# RainbowClock.net
KiCad netlist of a schematic drawn in Altium Designer
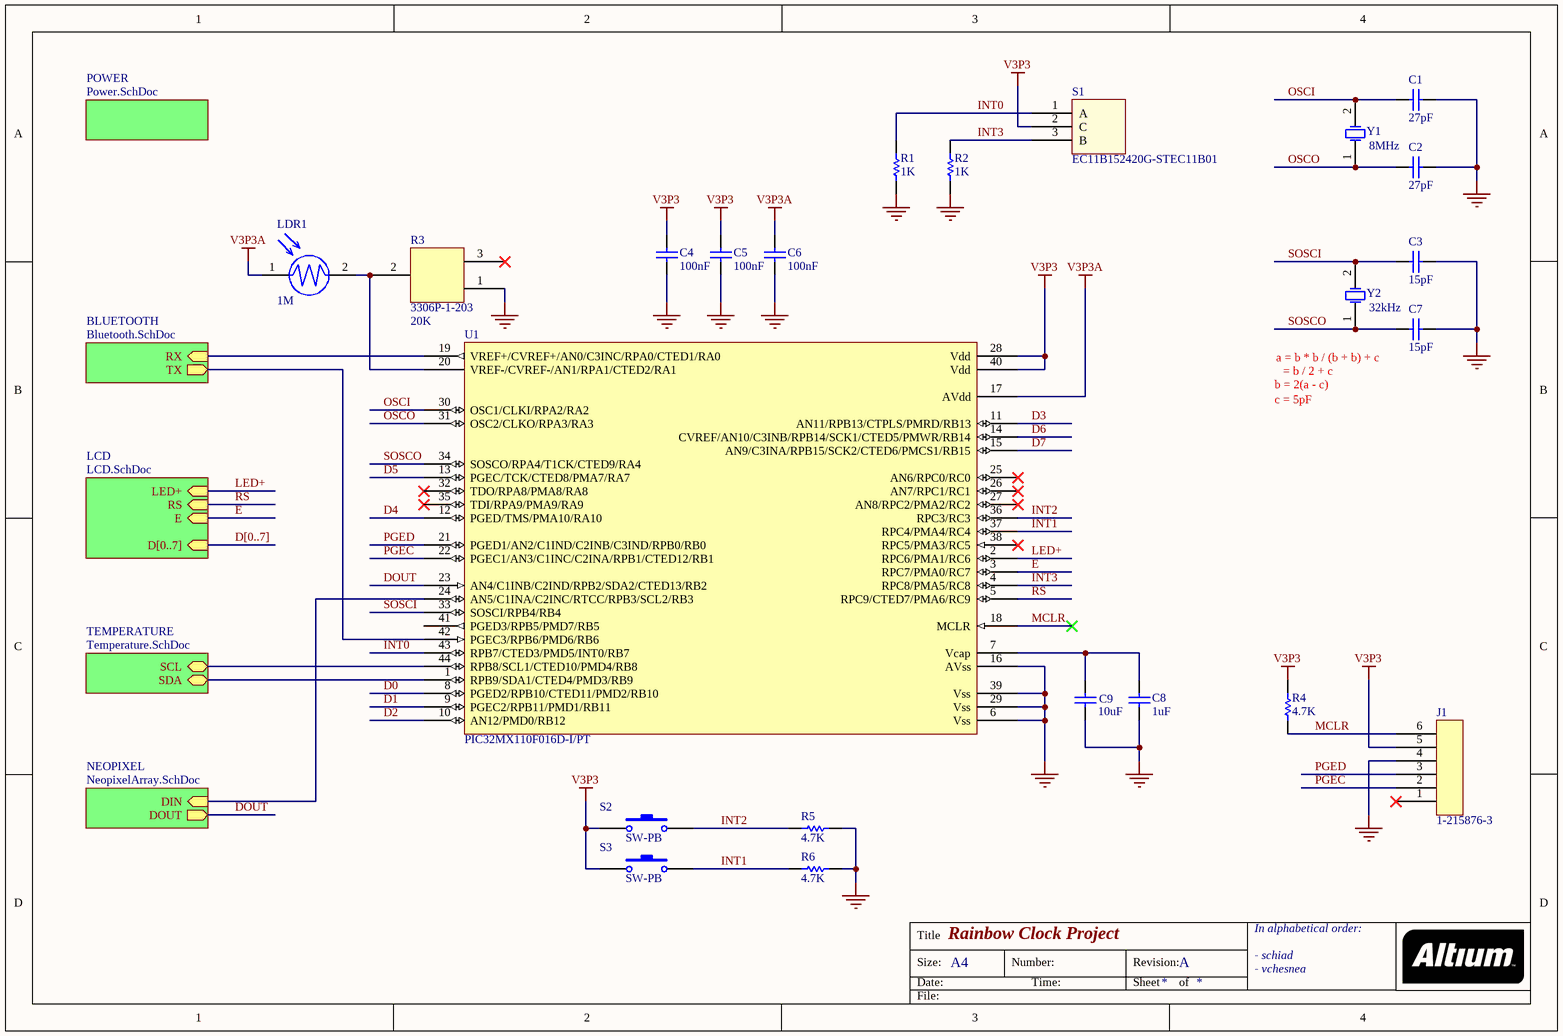
[diagram p0: RainbowClock.SchDoc]

(export (version "E")
  (design (tool "Eeschema 10.0.6"))
  (components
    (comp (ref "C1")
      (value "27pF")
      (footprint "CAP0603")
      (description "Capacitor")
      (libsource (lib "Miscellaneous Devices") (part "Cap"))
    )
    (comp (ref "C2")
      (value "27pF")
      (footprint "CAP0603")
      (description "Capacitor")
      (libsource (lib "Miscellaneous Devices") (part "Cap"))
    )
    (comp (ref "C3")
      (value "15pF")
      (footprint "CAP0603")
      (description "Capacitor")
      (libsource (lib "Miscellaneous Devices") (part "Cap"))
    )
    (comp (ref "C4")
      (value "100nF")
      (footprint "CAP0603")
      (description "Capacitor")
      (libsource (lib "Miscellaneous Devices") (part "Cap"))
    )
    (comp (ref "C5")
      (value "100nF")
      (footprint "CAP0603")
      (description "Capacitor")
      (libsource (lib "Miscellaneous Devices") (part "Cap"))
    )
    (comp (ref "C6")
      (value "100nF")
      (footprint "CAP0603")
      (description "Capacitor")
      (libsource (lib "Miscellaneous Devices") (part "Cap"))
    )
    (comp (ref "C7")
      (value "15pF")
      (footprint "CAP0603")
      (description "Capacitor")
      (libsource (lib "Miscellaneous Devices") (part "Cap"))
    )
    (comp (ref "C8")
      (value "1uF")
      (footprint "CAP0603")
      (description "Capacitor")
      (libsource (lib "Miscellaneous Devices") (part "Cap"))
    )
    (comp (ref "C9")
      (value "10uF")
      (footprint "CAP0603")
      (description "Capacitor")
      (libsource (lib "Miscellaneous Devices") (part "Cap"))
    )
    (comp (ref "J1")
      (value "1-215876-3")
      (footprint "1-215876-3")
      (description "Tyco 1-215876-3")
      (libsource (lib "Components") (part "1-215876-3"))
    )
    (comp (ref "LDR1")
      (value "1M")
      (footprint "VT935G")
      (description "Photoresistor")
      (fields (field (name "Comment") "LDR"))
      (libsource (lib "Components") (part "LDR"))
    )
    (comp (ref "R1")
      (value "1K")
      (footprint "RES0603")
      (description "Resistor")
      (libsource (lib "Miscellaneous Devices") (part "Res1"))
    )
    (comp (ref "R2")
      (value "1K")
      (footprint "RES0603")
      (description "Resistor")
      (libsource (lib "Miscellaneous Devices") (part "Res1"))
    )
    (comp (ref "R3")
      (value "3306P-1-203")
      (footprint "3306P-1-202")
      (description "Trimpot")
      (fields (field (name "ALTIUM_VALUE") "20K"))
      (libsource (lib "Components") (part "3306P-1-202"))
    )
    (comp (ref "R4")
      (value "4.7K")
      (footprint "RES0603")
      (description "Resistor")
      (libsource (lib "Miscellaneous Devices") (part "Res1"))
    )
    (comp (ref "R5")
      (value "4.7K")
      (footprint "RES0603")
      (description "Resistor")
      (libsource (lib "Miscellaneous Devices") (part "Res1"))
    )
    (comp (ref "R6")
      (value "4.7K")
      (footprint "RES0603")
      (description "Resistor")
      (libsource (lib "Miscellaneous Devices") (part "Res1"))
    )
    (comp (ref "S1")
      (value "EC11B152420G-STEC11B01")
      (footprint "EC11B152420G-STEC11B01")
      (description "Rotary encoder")
      (libsource (lib "Components") (part "EC11B152420G-STEC11B01"))
    )
    (comp (ref "S2")
      (value "SW-PB")
      (footprint "1-1825027-4")
      (description "Switch")
      (libsource (lib "Miscellaneous Devices") (part "SW-PB"))
    )
    (comp (ref "S3")
      (value "SW-PB")
      (footprint "1-1825027-4")
      (description "Switch")
      (libsource (lib "Miscellaneous Devices") (part "SW-PB"))
    )
    (comp (ref "U1")
      (value "PIC32MX110F016D-I/PT")
      (footprint "PIC32MX110F016H-I/PT")
      (description "Microcontroller")
      (libsource (lib "Components") (part "PIC32MX110F016D-I/PT"))
    )
    (comp (ref "Y1")
      (value "8MHz")
      (footprint "FOXSLF/080-20")
      (description "Crystal Oscillator")
      (fields (field (name "Comment") "8MHz XTAL"))
      (libsource (lib "Miscellaneous Devices") (part "XTAL"))
    )
    (comp (ref "Y2")
      (value "32kHz")
      (footprint "NCL38LF")
      (description "Crystal Oscillator")
      (fields (field (name "Comment") "32kHz XTAL"))
      (libsource (lib "Miscellaneous Devices") (part "XTAL"))
    )
  )
  (nets
    (net (code "1") (name "/D0") (class "Default")
      (node (ref "U1") (pin "8") (pinfunction "PGED2/RPB10/CTED11/PMD2/RB10_8") (pintype "bidirectional"))
    )
    (net (code "2") (name "/D1") (class "Default")
      (node (ref "U1") (pin "9") (pinfunction "PGEC2/RPB11/PMD1/RB11_9") (pintype "bidirectional"))
    )
    (net (code "3") (name "/D2") (class "Default")
      (node (ref "U1") (pin "10") (pinfunction "AN12/PMD0/RB12_10") (pintype "bidirectional"))
    )
    (net (code "4") (name "/D3") (class "Default")
      (node (ref "U1") (pin "11") (pinfunction "AN11/RPB13/CTPLS/PMRD/RB13_11") (pintype "bidirectional"))
    )
    (net (code "5") (name "/D4") (class "Default")
      (node (ref "U1") (pin "12") (pinfunction "PGED/TMS/PMA10/RA10_12") (pintype "bidirectional"))
    )
    (net (code "6") (name "/D5") (class "Default")
      (node (ref "U1") (pin "13") (pinfunction "PGEC/TCK/CTED8/PMA7/RA7_13") (pintype "bidirectional"))
    )
    (net (code "7") (name "/D6") (class "Default")
      (node (ref "U1") (pin "14") (pinfunction "CVREF/AN10/C3INB/RPB14/SCK1/CTED5/PMWR/RB14_14") (pintype "bidirectional"))
    )
    (net (code "8") (name "/D7") (class "Default")
      (node (ref "U1") (pin "15") (pinfunction "AN9/C3INA/RPB15/SCK2/CTED6/PMCS1/RB15_15") (pintype "bidirectional"))
    )
    (net (code "9") (name "/DIN") (class "Default")
      (node (ref "U1") (pin "24") (pinfunction "AN5/C1INA/C2INC/RTCC/RPB3/SCL2/RB3_24") (pintype "bidirectional"))
    )
    (net (code "10") (name "/DOUT") (class "Default")
      (node (ref "U1") (pin "23") (pinfunction "AN4/C1INB/C2IND/RPB2/SDA2/CTED13/RB2_23") (pintype "input"))
    )
    (net (code "12") (name "/E") (class "Default")
      (node (ref "U1") (pin "3") (pinfunction "RPC7/PMA0/RC7_3") (pintype "bidirectional"))
    )
    (net (code "13") (name "/INT0") (class "Default")
      (node (ref "R1") (pin "1") (pinfunction "1_1") (pintype "passive"))
      (node (ref "S1") (pin "1") (pinfunction "A_1") (pintype "passive"))
      (node (ref "U1") (pin "43") (pinfunction "RPB7/CTED3/PMD5/INT0/RB7_43") (pintype "bidirectional"))
    )
    (net (code "14") (name "/INT1") (class "Default")
      (node (ref "R6") (pin "2") (pinfunction "2_2") (pintype "passive"))
      (node (ref "S3") (pin "1") (pinfunction "1_1") (pintype "passive"))
      (node (ref "U1") (pin "37") (pinfunction "RPC4/PMA4/RC4_37") (pintype "bidirectional"))
    )
    (net (code "15") (name "/INT2") (class "Default")
      (node (ref "R5") (pin "2") (pinfunction "2_2") (pintype "passive"))
      (node (ref "S2") (pin "2") (pinfunction "2_2") (pintype "passive"))
      (node (ref "U1") (pin "36") (pinfunction "RPC3/RC3_36") (pintype "bidirectional"))
    )
    (net (code "16") (name "/INT3") (class "Default")
      (node (ref "R2") (pin "2") (pinfunction "2_2") (pintype "passive"))
      (node (ref "S1") (pin "3") (pinfunction "B_3") (pintype "passive"))
      (node (ref "U1") (pin "4") (pinfunction "RPC8/PMA5/RC8_4") (pintype "bidirectional"))
    )
    (net (code "17") (name "/LED+") (class "Default")
      (node (ref "U1") (pin "2") (pinfunction "RPC6/PMA1/RC6_2") (pintype "bidirectional"))
    )
    (net (code "18") (name "/MCLR") (class "Default")
      (node (ref "J1") (pin "6") (pintype "passive"))
      (node (ref "R4") (pin "1") (pinfunction "1_1") (pintype "passive"))
      (node (ref "U1") (pin "18") (pinfunction "MCLR_18") (pintype "input"))
    )
    (net (code "19") (name "/OSCI") (class "Default")
      (node (ref "C1") (pin "1") (pinfunction "1_1") (pintype "passive"))
      (node (ref "U1") (pin "30") (pinfunction "OSC1/CLKI/RPA2/RA2_30") (pintype "bidirectional"))
      (node (ref "Y1") (pin "2") (pinfunction "OSC2_2") (pintype "passive"))
    )
    (net (code "20") (name "/OSCO") (class "Default")
      (node (ref "C2") (pin "1") (pinfunction "1_1") (pintype "passive"))
      (node (ref "U1") (pin "31") (pinfunction "OSC2/CLKO/RPA3/RA3_31") (pintype "bidirectional"))
      (node (ref "Y1") (pin "1") (pinfunction "OSC1_1") (pintype "passive"))
    )
    (net (code "21") (name "/PGEC") (class "Default")
      (node (ref "J1") (pin "2") (pintype "passive"))
      (node (ref "U1") (pin "22") (pinfunction "PGEC1/AN3/C1INC/C2INA/RPB1/CTED12/RB1_22") (pintype "bidirectional"))
    )
    (net (code "22") (name "/PGED") (class "Default")
      (node (ref "J1") (pin "3") (pintype "passive"))
      (node (ref "U1") (pin "21") (pinfunction "PGED1/AN2/C1IND/C2INB/C3IND/RPB0/RB0_21") (pintype "bidirectional"))
    )
    (net (code "23") (name "/RS") (class "Default")
      (node (ref "U1") (pin "5") (pinfunction "RPC9/CTED7/PMA6/RC9_5") (pintype "bidirectional"))
    )
    (net (code "24") (name "/RX") (class "Default")
      (node (ref "U1") (pin "19") (pinfunction "VREF+/CVREF+/AN0/C3INC/RPA0/CTED1/RA0_19") (pintype "output"))
    )
    (net (code "25") (name "/SCL") (class "Default")
      (node (ref "U1") (pin "44") (pinfunction "RPB8/SCL1/CTED10/PMD4/RB8_44") (pintype "bidirectional"))
    )
    (net (code "26") (name "/SDA") (class "Default")
      (node (ref "U1") (pin "1") (pinfunction "RPB9/SDA1/CTED4/PMD3/RB9_1") (pintype "bidirectional"))
    )
    (net (code "27") (name "/SOSCI") (class "Default")
      (node (ref "C3") (pin "1") (pinfunction "1_1") (pintype "passive"))
      (node (ref "U1") (pin "33") (pinfunction "SOSCI/RPB4/RB4_33") (pintype "bidirectional"))
      (node (ref "Y2") (pin "2") (pinfunction "OSC2_2") (pintype "passive"))
    )
    (net (code "28") (name "/SOSCO") (class "Default")
      (node (ref "C7") (pin "1") (pinfunction "1_1") (pintype "passive"))
      (node (ref "U1") (pin "34") (pinfunction "SOSCO/RPA4/T1CK/CTED9/RA4_34") (pintype "bidirectional"))
      (node (ref "Y2") (pin "1") (pinfunction "OSC1_1") (pintype "passive"))
    )
    (net (code "29") (name "/TX") (class "Default")
      (node (ref "U1") (pin "42") (pinfunction "PGEC3/RPB6/PMD6/RB6_42") (pintype "input"))
    )
    (net (code "30") (name "GND") (class "Default")
      (node (ref "C1") (pin "2") (pinfunction "2_2") (pintype "passive"))
      (node (ref "C2") (pin "2") (pinfunction "2_2") (pintype "passive"))
      (node (ref "C3") (pin "2") (pinfunction "2_2") (pintype "passive"))
      (node (ref "C4") (pin "1") (pinfunction "1_1") (pintype "passive"))
      (node (ref "C5") (pin "1") (pinfunction "1_1") (pintype "passive"))
      (node (ref "C6") (pin "1") (pinfunction "1_1") (pintype "passive"))
      (node (ref "C7") (pin "2") (pinfunction "2_2") (pintype "passive"))
      (node (ref "C8") (pin "1") (pinfunction "1_1") (pintype "passive"))
      (node (ref "C9") (pin "1") (pinfunction "1_1") (pintype "passive"))
      (node (ref "J1") (pin "4") (pintype "passive"))
      (node (ref "R1") (pin "2") (pinfunction "2_2") (pintype "passive"))
      (node (ref "R2") (pin "1") (pinfunction "1_1") (pintype "passive"))
      (node (ref "R3") (pin "1") (pinfunction "1_1") (pintype "power_in"))
      (node (ref "R5") (pin "1") (pinfunction "1_1") (pintype "passive"))
      (node (ref "R6") (pin "1") (pinfunction "1_1") (pintype "passive"))
      (node (ref "U1") (pin "16") (pinfunction "AVss_16") (pintype "power_in"))
      (node (ref "U1") (pin "29") (pinfunction "Vss_29") (pintype "power_in"))
      (node (ref "U1") (pin "39") (pinfunction "Vss_39") (pintype "power_in"))
      (node (ref "U1") (pin "6") (pinfunction "Vss_6") (pintype "passive"))
    )
    (net (code "31") (name "Net-(U1-VREF-{slash}CVREF-{slash}AN1{slash}RPA1{slash}CTED2{slash}RA1)") (class "Default")
      (node (ref "LDR1") (pin "2") (pinfunction "2_2") (pintype "power_in"))
      (node (ref "R3") (pin "2") (pinfunction "2_2") (pintype "power_in"))
      (node (ref "U1") (pin "20") (pinfunction "VREF-/CVREF-/AN1/RPA1/CTED2/RA1_20") (pintype "passive"))
    )
    (net (code "32") (name "Net-(U1-Vcap)") (class "Default")
      (node (ref "C8") (pin "2") (pinfunction "2_2") (pintype "passive"))
      (node (ref "C9") (pin "2") (pinfunction "2_2") (pintype "passive"))
      (node (ref "U1") (pin "7") (pinfunction "Vcap_7") (pintype "passive"))
    )
    (net (code "33") (name "V3P3") (class "Default")
      (node (ref "C4") (pin "2") (pinfunction "2_2") (pintype "passive"))
      (node (ref "C5") (pin "2") (pinfunction "2_2") (pintype "passive"))
      (node (ref "J1") (pin "5") (pintype "passive"))
      (node (ref "R4") (pin "2") (pinfunction "2_2") (pintype "passive"))
      (node (ref "S1") (pin "2") (pinfunction "C_2") (pintype "passive"))
      (node (ref "S2") (pin "1") (pinfunction "1_1") (pintype "passive"))
      (node (ref "S3") (pin "2") (pinfunction "2_2") (pintype "passive"))
      (node (ref "U1") (pin "28") (pinfunction "Vdd_28") (pintype "power_in"))
      (node (ref "U1") (pin "40") (pinfunction "Vdd_40") (pintype "power_in"))
    )
    (net (code "34") (name "V3P3A") (class "Default")
      (node (ref "C6") (pin "2") (pinfunction "2_2") (pintype "passive"))
      (node (ref "LDR1") (pin "1") (pinfunction "1_1") (pintype "power_in"))
      (node (ref "U1") (pin "17") (pinfunction "AVdd_17") (pintype "power_in"))
    )
    (net (code "35") (name "unconnected-(J1-Pad1)") (class "Default")
      (node (ref "J1") (pin "1") (pintype "passive+no_connect"))
    )
    (net (code "36") (name "unconnected-(R3-Pad3)") (class "Default")
      (node (ref "R3") (pin "3") (pinfunction "3_3") (pintype "power_in+no_connect"))
    )
    (net (code "37") (name "unconnected-(U1-AN6{slash}RPC0{slash}RC0-Pad25)") (class "Default")
      (node (ref "U1") (pin "25") (pinfunction "AN6/RPC0/RC0_25") (pintype "bidirectional+no_connect"))
    )
    (net (code "38") (name "unconnected-(U1-AN7{slash}RPC1{slash}RC1-Pad26)") (class "Default")
      (node (ref "U1") (pin "26") (pinfunction "AN7/RPC1/RC1_26") (pintype "bidirectional+no_connect"))
    )
    (net (code "39") (name "unconnected-(U1-AN8{slash}RPC2{slash}PMA2{slash}RC2-Pad27)") (class "Default")
      (node (ref "U1") (pin "27") (pinfunction "AN8/RPC2/PMA2/RC2_27") (pintype "bidirectional+no_connect"))
    )
    (net (code "40") (name "unconnected-(U1-PGED3{slash}RPB5{slash}PMD7{slash}RB5-Pad41)") (class "Default")
      (node (ref "U1") (pin "41") (pinfunction "PGED3/RPB5/PMD7/RB5_41") (pintype "output"))
    )
    (net (code "41") (name "unconnected-(U1-RPC5{slash}PMA3{slash}RC5-Pad38)") (class "Default")
      (node (ref "U1") (pin "38") (pinfunction "RPC5/PMA3/RC5_38") (pintype "input+no_connect"))
    )
    (net (code "42") (name "unconnected-(U1-TDI{slash}RPA9{slash}PMA9{slash}RA9-Pad35)") (class "Default")
      (node (ref "U1") (pin "35") (pinfunction "TDI/RPA9/PMA9/RA9_35") (pintype "bidirectional+no_connect"))
    )
    (net (code "43") (name "unconnected-(U1-TDO{slash}RPA8{slash}PMA8{slash}RA8-Pad32)") (class "Default")
      (node (ref "U1") (pin "32") (pinfunction "TDO/RPA8/PMA8/RA8_32") (pintype "bidirectional+no_connect"))
    )
  )
)
